# SIDE-BRUSH-MOTORs.net
KiCad netlist of a schematic drawn in Altium Designer
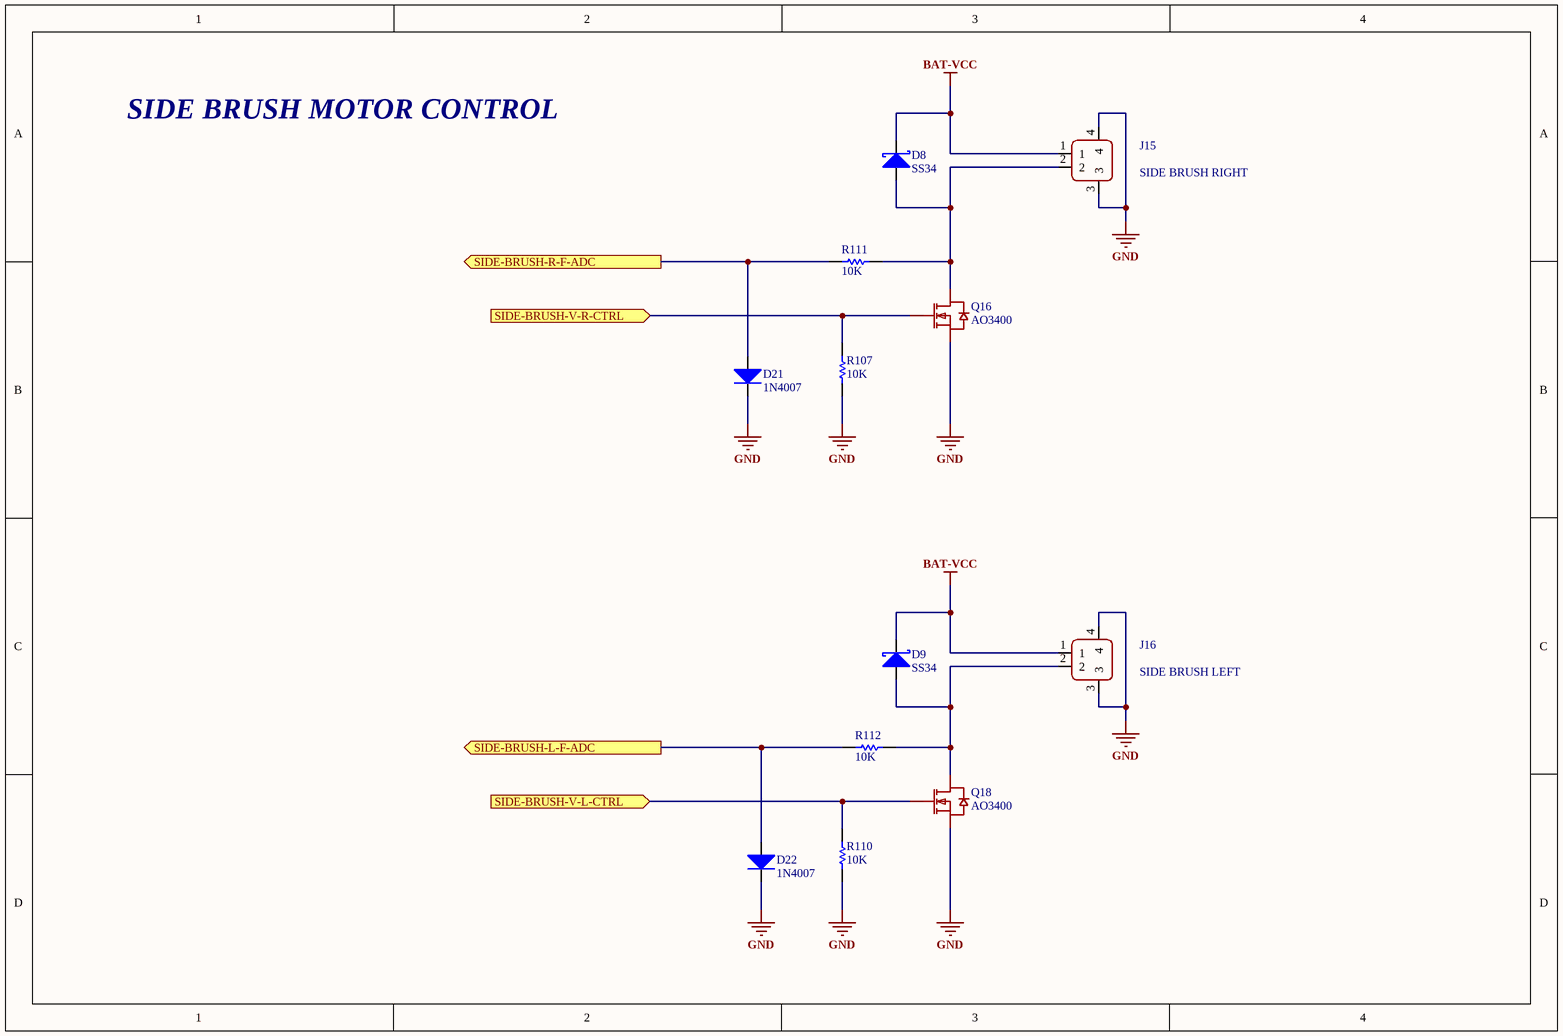
[diagram p0: SIDE-BRUSH-MOTORs .SchDoc]

(export (version "E")
  (design (tool "Eeschema 10.0.6"))
  (components
    (comp (ref "D8") (value "SS34") (footprint "SMA") (libsource (lib "DesignLibrary") (part "DIODE-2")))
    (comp (ref "D9") (value "SS34") (footprint "SMA") (libsource (lib "DesignLibrary") (part "DIODE-2")))
    (comp (ref "D21")
      (value "1N4007")
      (footprint "SOD123")
      (libsource (lib "DesignLibrary") (part "DIODE-1"))
    )
    (comp (ref "D22")
      (value "1N4007")
      (footprint "SOD123")
      (libsource (lib "DesignLibrary") (part "DIODE-1"))
    )
    (comp (ref "J15")
      (value "SIDE BRUSH RIGHT")
      (footprint "CONN-SMD_2P-P1.50_ZX-ZH1.5-2PWT")
      (libsource (lib "DesignLibrary") (part "HDRx2"))
    )
    (comp (ref "J16")
      (value "SIDE BRUSH LEFT")
      (footprint "CONN-SMD_2P-P1.50_ZX-ZH1.5-2PWT")
      (libsource (lib "DesignLibrary") (part "HDRx2"))
    )
    (comp (ref "Q16")
      (value "AO3400")
      (footprint "SOT23-3D")
      (libsource (lib "DesignLibrary") (part "N-MOS-SOT23"))
    )
    (comp (ref "Q18")
      (value "AO3400")
      (footprint "SOT23-3D")
      (libsource (lib "DesignLibrary") (part "N-MOS-SOT23"))
    )
    (comp (ref "R107")
      (value "10K")
      (footprint "RES-0402")
      (libsource (lib "DesignLibrary") (part "Resistor-1"))
    )
    (comp (ref "R110")
      (value "10K")
      (footprint "RES-0402")
      (libsource (lib "DesignLibrary") (part "Resistor-1"))
    )
    (comp (ref "R111")
      (value "10K")
      (footprint "RES-0402")
      (libsource (lib "DesignLibrary") (part "Resistor-1"))
    )
    (comp (ref "R112")
      (value "10K")
      (footprint "RES-0402")
      (libsource (lib "DesignLibrary") (part "Resistor-1"))
    )
  )
  (nets
    (net (code "1") (name "/SIDE-BRUSH-L-F-ADC") (class "Default")
      (node (ref "D22") (pin "1") (pinfunction "A_1") (pintype "passive"))
      (node (ref "R112") (pin "2") (pintype "passive"))
    )
    (net (code "2") (name "/SIDE-BRUSH-R-F-ADC") (class "Default")
      (node (ref "D21") (pin "1") (pinfunction "A_1") (pintype "passive"))
      (node (ref "R111") (pin "2") (pintype "passive"))
    )
    (net (code "3") (name "/SIDE-BRUSH-V-L-CTRL") (class "Default")
      (node (ref "Q18") (pin "1") (pinfunction "G_1") (pintype "passive"))
      (node (ref "R110") (pin "2") (pintype "passive"))
    )
    (net (code "4") (name "/SIDE-BRUSH-V-R-CTRL") (class "Default")
      (node (ref "Q16") (pin "1") (pinfunction "G_1") (pintype "passive"))
      (node (ref "R107") (pin "2") (pintype "passive"))
    )
    (net (code "5") (name "BAT-VCC") (class "Default")
      (node (ref "D8") (pin "2") (pinfunction "K_2") (pintype "passive"))
      (node (ref "D9") (pin "2") (pinfunction "K_2") (pintype "passive"))
      (node (ref "J15") (pin "1") (pinfunction "1_1") (pintype "passive"))
      (node (ref "J16") (pin "1") (pinfunction "1_1") (pintype "passive"))
    )
    (net (code "6") (name "GND") (class "Default")
      (node (ref "D21") (pin "2") (pinfunction "K_2") (pintype "passive"))
      (node (ref "D22") (pin "2") (pinfunction "K_2") (pintype "passive"))
      (node (ref "J15") (pin "3") (pinfunction "3_3") (pintype "passive"))
      (node (ref "J15") (pin "4") (pinfunction "4_4") (pintype "passive"))
      (node (ref "J16") (pin "3") (pinfunction "3_3") (pintype "passive"))
      (node (ref "J16") (pin "4") (pinfunction "4_4") (pintype "passive"))
      (node (ref "Q16") (pin "2") (pinfunction "S_2") (pintype "passive"))
      (node (ref "Q18") (pin "2") (pinfunction "S_2") (pintype "passive"))
      (node (ref "R107") (pin "1") (pintype "passive"))
      (node (ref "R110") (pin "1") (pintype "passive"))
    )
    (net (code "7") (name "Net-(D8-A)") (class "Default")
      (node (ref "D8") (pin "1") (pinfunction "A_1") (pintype "passive"))
      (node (ref "J15") (pin "2") (pinfunction "2_2") (pintype "passive"))
      (node (ref "Q16") (pin "3") (pinfunction "D_3") (pintype "passive"))
      (node (ref "R111") (pin "1") (pintype "passive"))
    )
    (net (code "8") (name "Net-(D9-A)") (class "Default")
      (node (ref "D9") (pin "1") (pinfunction "A_1") (pintype "passive"))
      (node (ref "J16") (pin "2") (pinfunction "2_2") (pintype "passive"))
      (node (ref "Q18") (pin "3") (pinfunction "D_3") (pintype "passive"))
      (node (ref "R112") (pin "1") (pintype "passive"))
    )
  )
)
